# Arduino_Connectors.net
KiCad netlist of a schematic drawn in Altium Designer
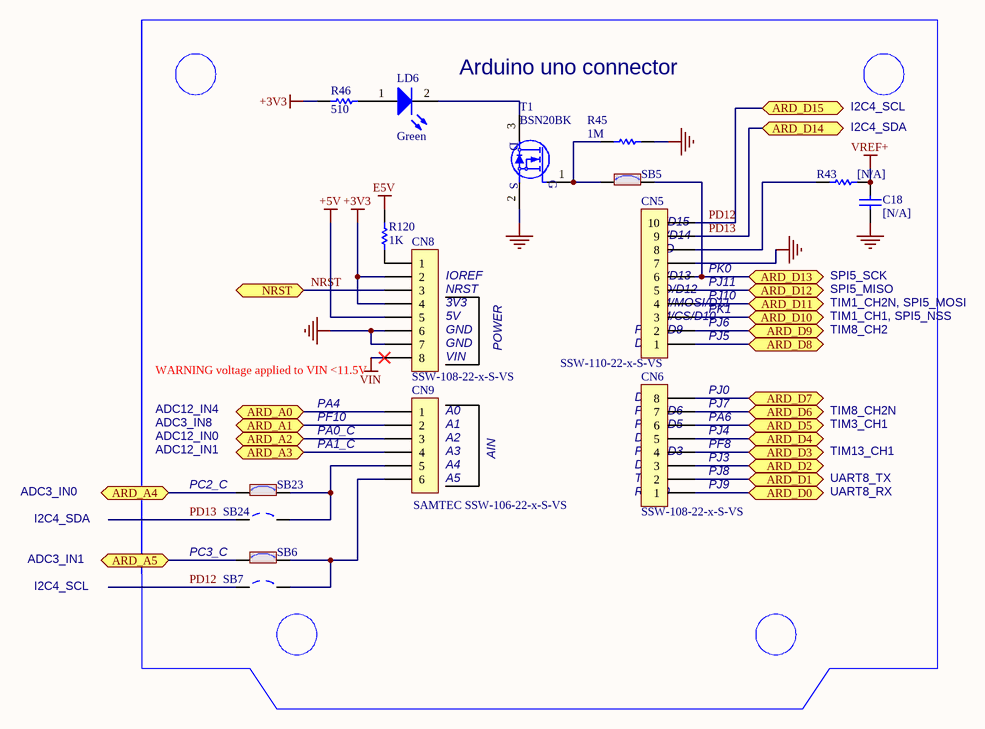
[diagram p0: Arduino Connectors.SchDoc]

(export (version "E")
  (design (tool "Eeschema 10.0.6"))
  (components
    (comp (ref "C18")
      (value "[N/A]")
      (footprint "0603C")
      (description "Capacitor")
      (fields (field (name "PUBLISHER") "Altium Limited"))
      (libsource (lib "Miscellaneous Devices") (part "Cap"))
    )
    (comp (ref "CN5")
      (value "SSW-110-22-x-S-VS")
      (footprint "SSW-110-22-X-S-VS")
      (description "Header, 10-Pin, Single row,female")
      (fields (field (name "PUBLISHER") "Altium Limited"))
      (libsource (lib "Nucleo_64") (part "Header 10X1_Female"))
    )
    (comp (ref "CN6")
      (value "SSW-108-22-x-S-VS")
      (footprint "SSW-108-22-X-S-VS")
      (description "Header, 8-Pin, Single row,female")
      (fields (field (name "PUBLISHER") "Altium Limited"))
      (libsource (lib "") (part "Header 8X1_Female_1"))
    )
    (comp (ref "CN8")
      (value "SSW-108-22-x-S-VS")
      (footprint "SSW-108-22-X-S-VS")
      (description "Header, 8-Pin, Single row,female")
      (fields (field (name "PUBLISHER") "Altium Limited"))
      (libsource (lib "Nucleo_64") (part "Header 8X1_Female"))
    )
    (comp (ref "CN9")
      (value "SAMTEC SSW-106-22-x-S-VS")
      (footprint "SSW-106-22-X-S-VS")
      (description "Header, 6-Pin, Single row,female SMD")
      (fields (field (name "PUBLISHER") "Altium Limited"))
      (libsource (lib "Nucleo_64") (part "Header 6X1_Female"))
    )
    (comp (ref "LD6")
      (value "Green")
      (footprint "0603D")
      (description "Typical RED, GREEN, YELLOW, AMBER GaAs LED")
      (fields (field (name "PUBLISHER") "Altium Limited"))
      (libsource (lib "Miscellaneous Devices") (part "LED2"))
    )
    (comp (ref "R43")
      (value "[N/A]")
      (footprint "0603R")
      (description "Resistor")
      (fields (field (name "PUBLISHER") "Altium Limited"))
      (libsource (lib "Miscellaneous Devices") (part "res1"))
    )
    (comp (ref "R45")
      (value "1M")
      (footprint "0603R")
      (description "Resistor, 1M , 0603")
      (fields (field (name "PUBLISHER") "Altium Limited"))
      (libsource (lib "Miscellaneous Devices") (part "res1"))
    )
    (comp (ref "R46")
      (value "510")
      (footprint "0603R")
      (description "Resistor")
      (fields (field (name "PUBLISHER") "Altium Limited"))
      (libsource (lib "Miscellaneous Devices") (part "Res1"))
    )
    (comp (ref "R120")
      (value "1K")
      (footprint "0603R")
      (description "Resistor")
      (fields (field (name "PUBLISHER") "Altium Limited"))
      (libsource (lib "Miscellaneous Devices") (part "res1"))
    )
    (comp (ref "SB5")
      (value "Solder Bridge ON")
      (footprint "SB_0603")
      (libsource (lib "MCD_TOOLS") (part "SB_ON"))
    )
    (comp (ref "SB6")
      (value "Solder Bridge ON")
      (footprint "SB_0603")
      (libsource (lib "MCD_TOOLS") (part "SB_ON"))
    )
    (comp (ref "SB7")
      (value "Solder Bridge OFF")
      (footprint "SB_0603")
      (libsource (lib "MCD_TOOLS") (part "SB_OFF"))
    )
    (comp (ref "SB23")
      (value "Solder Bridge ON")
      (footprint "SB_0603")
      (libsource (lib "MCD_TOOLS") (part "SB_ON"))
    )
    (comp (ref "SB24")
      (value "Solder Bridge OFF")
      (footprint "SB_0603")
      (libsource (lib "MCD_TOOLS") (part "SB_OFF"))
    )
    (comp (ref "T1") (value "BSN20BK") (footprint "SOT-23") (libsource (lib "MB525") (part "2N7000")))
  )
  (nets
    (net (code "1") (name "+3V3") (class "Default")
      (node (ref "CN8") (pin "2") (pinfunction "2_2") (pintype "passive"))
      (node (ref "CN8") (pin "4") (pinfunction "4_4") (pintype "passive"))
      (node (ref "R46") (pin "2") (pinfunction "2_2") (pintype "passive"))
    )
    (net (code "2") (name "+5V") (class "Default")
      (node (ref "CN8") (pin "5") (pinfunction "5_5") (pintype "passive"))
    )
    (net (code "3") (name "/ARD_A0") (class "Default")
      (node (ref "CN9") (pin "1") (pinfunction "1_1") (pintype "passive"))
    )
    (net (code "4") (name "/ARD_A1") (class "Default")
      (node (ref "CN9") (pin "2") (pinfunction "2_2") (pintype "passive"))
    )
    (net (code "5") (name "/ARD_A2") (class "Default")
      (node (ref "CN9") (pin "3") (pinfunction "3_3") (pintype "passive"))
    )
    (net (code "6") (name "/ARD_A3") (class "Default")
      (node (ref "CN9") (pin "4") (pinfunction "4_4") (pintype "passive"))
    )
    (net (code "7") (name "/ARD_A4") (class "Default")
      (node (ref "SB23") (pin "1") (pinfunction "1_1") (pintype "passive"))
    )
    (net (code "8") (name "/ARD_A5") (class "Default")
      (node (ref "SB6") (pin "1") (pinfunction "1_1") (pintype "passive"))
    )
    (net (code "9") (name "/ARD_D0") (class "Default")
      (node (ref "CN6") (pin "1") (pinfunction "1_1") (pintype "passive"))
    )
    (net (code "10") (name "/ARD_D1") (class "Default")
      (node (ref "CN6") (pin "2") (pinfunction "2_2") (pintype "passive"))
    )
    (net (code "11") (name "/ARD_D2") (class "Default")
      (node (ref "CN6") (pin "3") (pinfunction "3_3") (pintype "passive"))
    )
    (net (code "12") (name "/ARD_D3") (class "Default")
      (node (ref "CN6") (pin "4") (pinfunction "4_4") (pintype "passive"))
    )
    (net (code "13") (name "/ARD_D4") (class "Default")
      (node (ref "CN6") (pin "5") (pinfunction "5_5") (pintype "passive"))
    )
    (net (code "14") (name "/ARD_D5") (class "Default")
      (node (ref "CN6") (pin "6") (pinfunction "6_6") (pintype "passive"))
    )
    (net (code "15") (name "/ARD_D6") (class "Default")
      (node (ref "CN6") (pin "7") (pinfunction "7_7") (pintype "passive"))
    )
    (net (code "16") (name "/ARD_D7") (class "Default")
      (node (ref "CN6") (pin "8") (pinfunction "8_8") (pintype "passive"))
    )
    (net (code "17") (name "/ARD_D8") (class "Default")
      (node (ref "CN5") (pin "1") (pinfunction "1_1") (pintype "passive"))
    )
    (net (code "18") (name "/ARD_D9") (class "Default")
      (node (ref "CN5") (pin "2") (pinfunction "2_2") (pintype "passive"))
    )
    (net (code "19") (name "/ARD_D10") (class "Default")
      (node (ref "CN5") (pin "3") (pinfunction "3_3") (pintype "passive"))
    )
    (net (code "20") (name "/ARD_D11") (class "Default")
      (node (ref "CN5") (pin "4") (pinfunction "4_4") (pintype "passive"))
    )
    (net (code "21") (name "/ARD_D12") (class "Default")
      (node (ref "CN5") (pin "5") (pinfunction "5_5") (pintype "passive"))
    )
    (net (code "22") (name "/ARD_D13") (class "Default")
      (node (ref "CN5") (pin "6") (pinfunction "6_6") (pintype "passive"))
      (node (ref "SB5") (pin "2") (pinfunction "2_2") (pintype "passive"))
    )
    (net (code "23") (name "/NRST") (class "Default")
      (node (ref "CN8") (pin "3") (pinfunction "3_3") (pintype "passive"))
    )
    (net (code "24") (name "/PD12") (class "Default")
      (node (ref "CN5") (pin "10") (pinfunction "10_10") (pintype "passive"))
      (node (ref "SB7") (pin "1") (pinfunction "1_1") (pintype "passive"))
    )
    (net (code "25") (name "/PD13") (class "Default")
      (node (ref "CN5") (pin "9") (pinfunction "9_9") (pintype "passive"))
      (node (ref "SB24") (pin "1") (pinfunction "1_1") (pintype "passive"))
    )
    (net (code "26") (name "E5V") (class "Default")
      (node (ref "R120") (pin "1") (pinfunction "1_1") (pintype "passive"))
    )
    (net (code "27") (name "GND") (class "Default")
      (node (ref "C18") (pin "1") (pinfunction "1_1") (pintype "passive"))
      (node (ref "CN5") (pin "7") (pinfunction "7_7") (pintype "passive"))
      (node (ref "CN8") (pin "6") (pinfunction "6_6") (pintype "passive"))
      (node (ref "CN8") (pin "7") (pinfunction "7_7") (pintype "passive"))
      (node (ref "R45") (pin "2") (pinfunction "2_2") (pintype "passive"))
      (node (ref "T1") (pin "2") (pinfunction "S_2") (pintype "passive"))
    )
    (net (code "28") (name "Net-(CN5-Pad8)") (class "Default")
      (node (ref "CN5") (pin "8") (pinfunction "8_8") (pintype "passive"))
      (node (ref "R43") (pin "1") (pinfunction "1_1") (pintype "passive"))
    )
    (net (code "29") (name "Net-(CN8-Pad1)") (class "Default")
      (node (ref "CN8") (pin "1") (pinfunction "1_1") (pintype "passive"))
      (node (ref "R120") (pin "2") (pinfunction "2_2") (pintype "passive"))
    )
    (net (code "30") (name "Net-(CN9-Pad5)") (class "Default")
      (node (ref "CN9") (pin "5") (pinfunction "5_5") (pintype "passive"))
      (node (ref "SB23") (pin "2") (pinfunction "2_2") (pintype "passive"))
      (node (ref "SB24") (pin "2") (pinfunction "2_2") (pintype "passive"))
    )
    (net (code "31") (name "Net-(CN9-Pad6)") (class "Default")
      (node (ref "CN9") (pin "6") (pinfunction "6_6") (pintype "passive"))
      (node (ref "SB6") (pin "2") (pinfunction "2_2") (pintype "passive"))
      (node (ref "SB7") (pin "2") (pinfunction "2_2") (pintype "passive"))
    )
    (net (code "32") (name "Net-(LD6-A)") (class "Default")
      (node (ref "LD6") (pin "1") (pinfunction "A_1") (pintype "passive"))
      (node (ref "R46") (pin "1") (pinfunction "1_1") (pintype "passive"))
    )
    (net (code "33") (name "Net-(LD6-K)") (class "Default")
      (node (ref "LD6") (pin "2") (pinfunction "K_2") (pintype "passive"))
      (node (ref "T1") (pin "3") (pinfunction "D_3") (pintype "passive"))
    )
    (net (code "34") (name "Net-(T1-G)") (class "Default")
      (node (ref "R45") (pin "1") (pinfunction "1_1") (pintype "passive"))
      (node (ref "SB5") (pin "1") (pinfunction "1_1") (pintype "passive"))
      (node (ref "T1") (pin "1") (pinfunction "G_1") (pintype "passive"))
    )
    (net (code "35") (name "VIN") (class "Default")
      (node (ref "CN8") (pin "8") (pinfunction "8_8") (pintype "passive"))
    )
    (net (code "36") (name "VREF+") (class "Default")
      (node (ref "C18") (pin "2") (pinfunction "2_2") (pintype "passive"))
      (node (ref "R43") (pin "2") (pinfunction "2_2") (pintype "passive"))
    )
  )
)
